# SCH_NFC-Business-Card_2025-04-14.net
KiCad netlist of a schematic drawn in EasyEDA
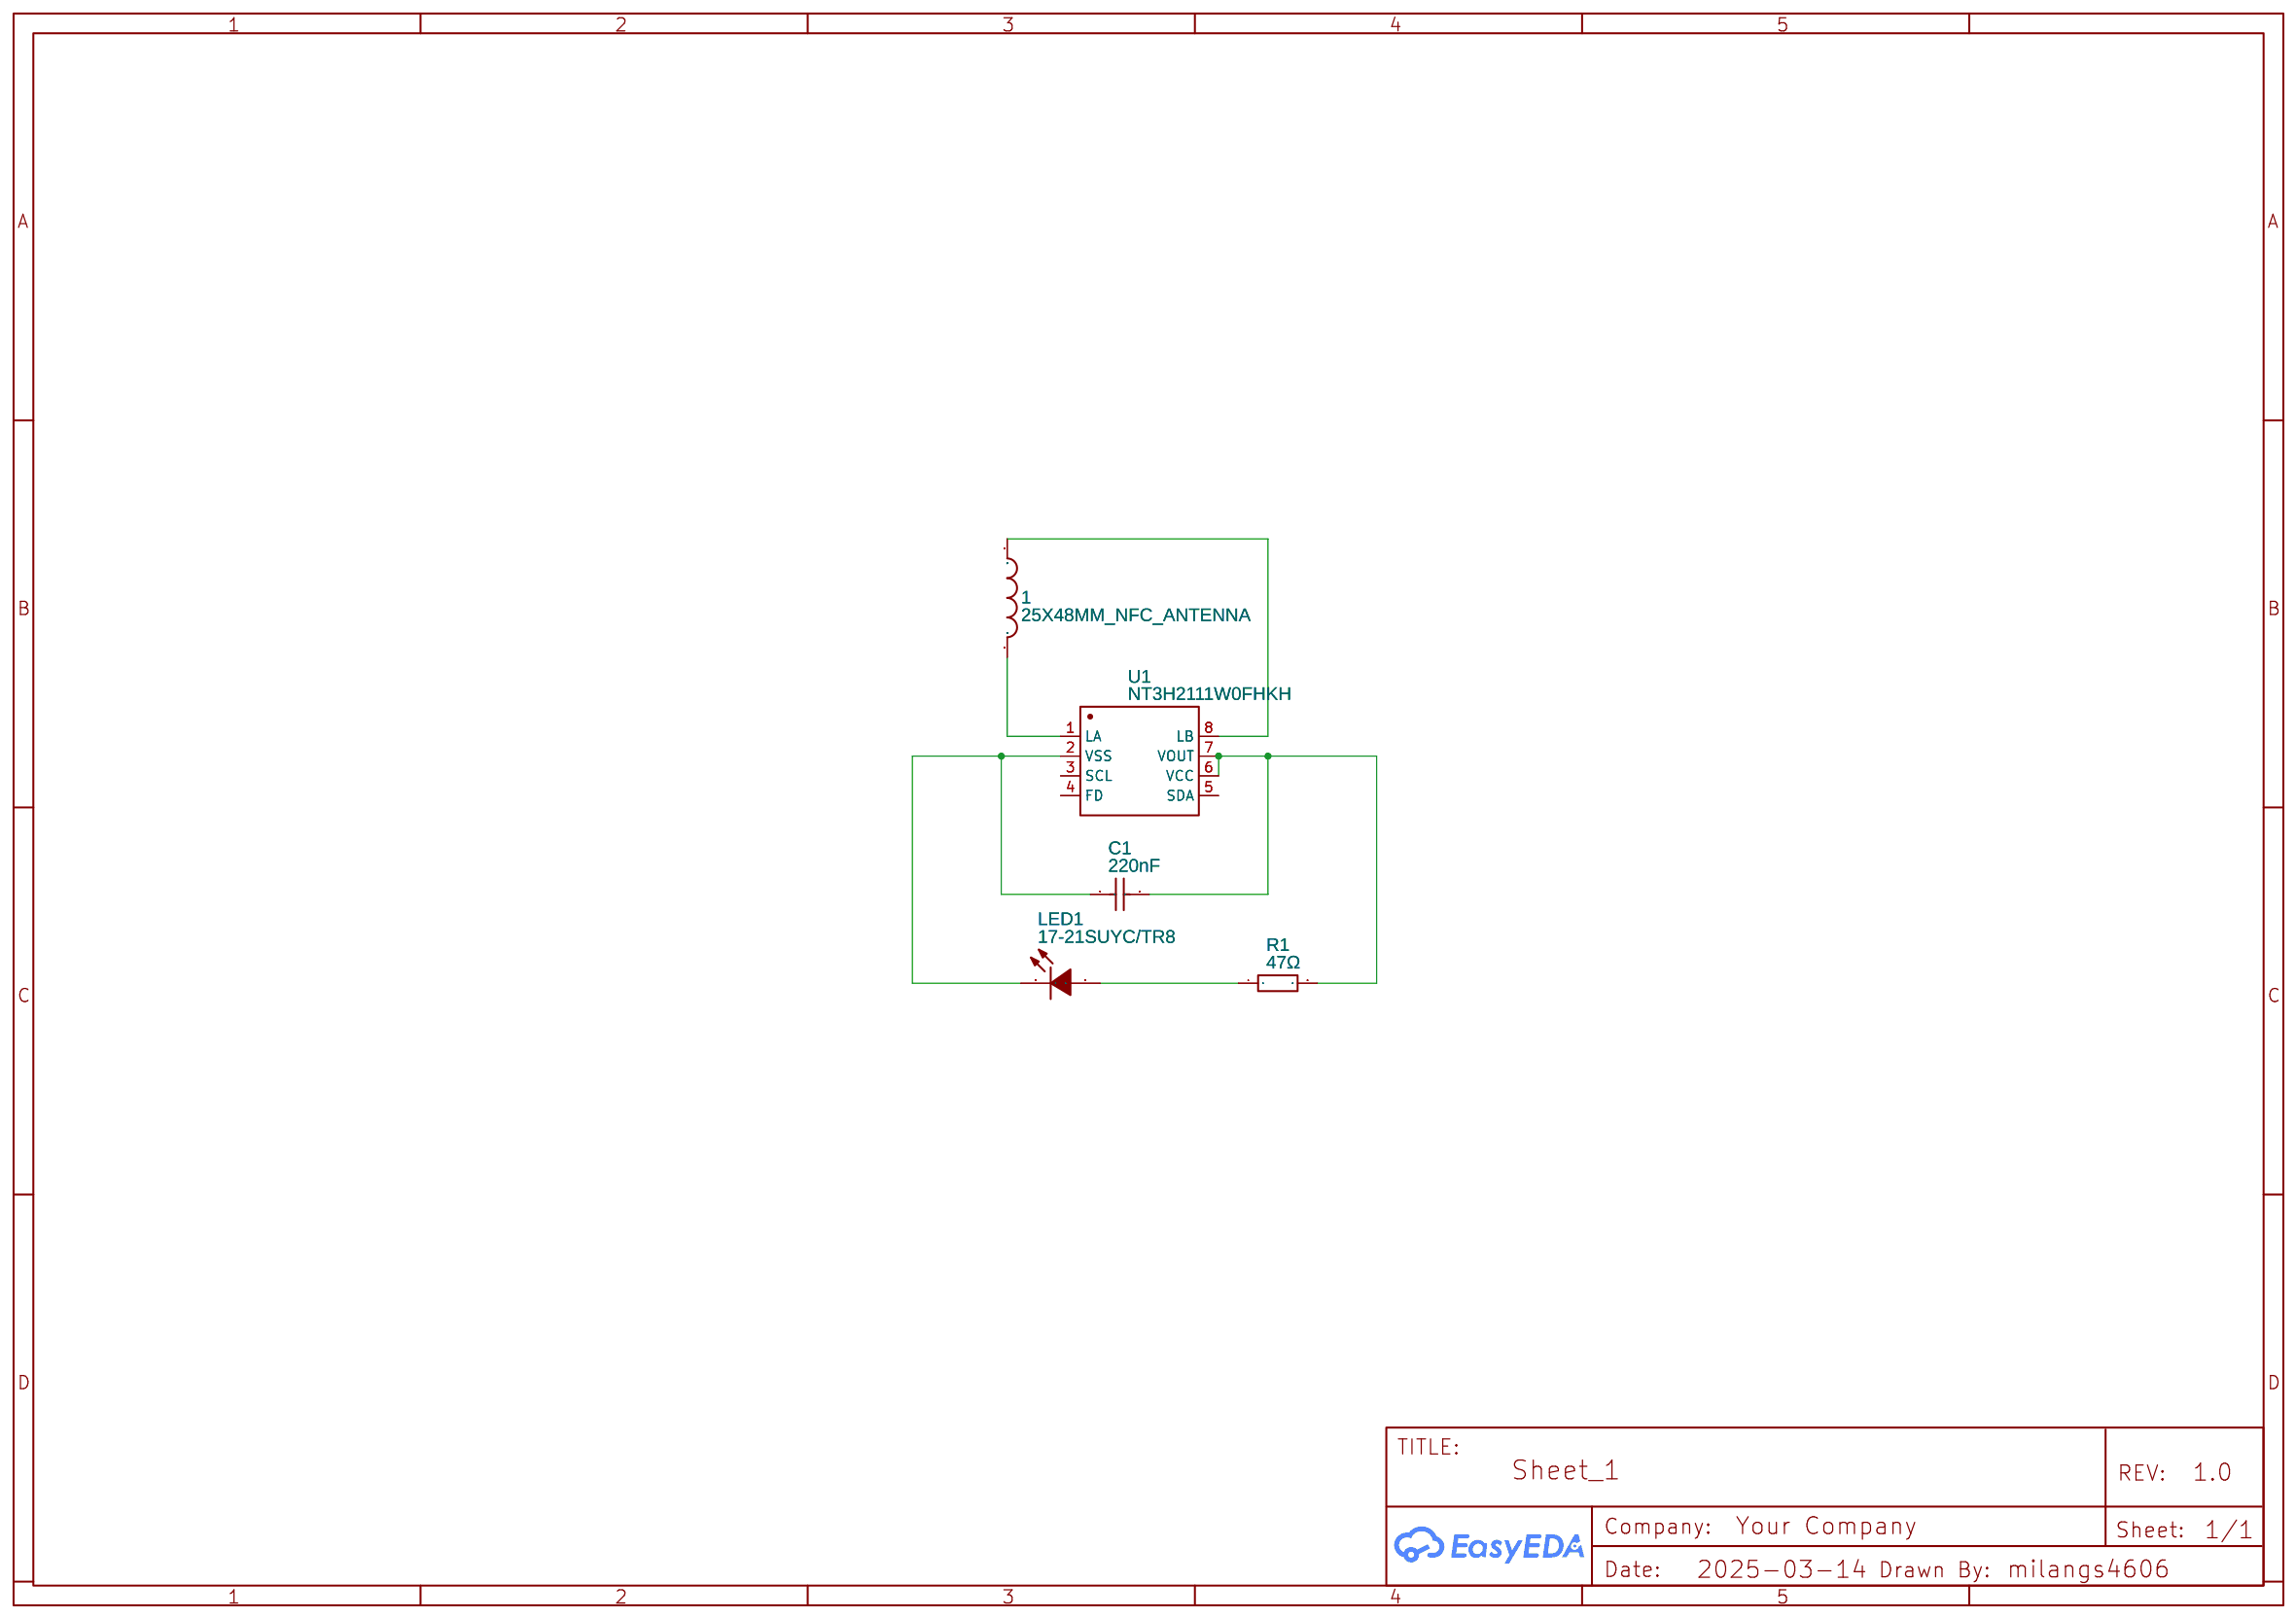
[diagram p0: schematic sheet]

(export (version "E")
  (design (tool "Eeschema 10.0.6"))
  (components
    (comp (ref "1") (value "25X48MM_NFC_ANTENNA") (libsource (lib "") (part "25X48MM_NFC_ANTENNA")))
    (comp (ref "C1")
      (value "220nF")
      (fields
        (field (name "Manufacturer Part") "CL10B224KA8NNNC")
        (field (name "Manufacturer") "SAMSUNG(三星)")
      )
      (libsource (lib "") (part "CL10B224KA8NNNC"))
    )
    (comp (ref "LED1")
      (value "17-21SUYC/TR8")
      (fields (field (name "Manufacturer Part") "KT-0805黄灯") (field (name "Manufacturer") "KENTO"))
      (libsource (lib "") (part "17-21SUYC/TR8"))
    )
    (comp (ref "R1")
      (value "47Ω")
      (fields
        (field (name "Manufacturer Part") "0603WAF470JT5E")
        (field (name "Manufacturer") "UNI-ROYAL(厚声)")
      )
      (libsource (lib "") (part "0603WAF470JT5E"))
    )
    (comp (ref "U1")
      (value "NT3H2111W0FHKH")
      (fields (field (name "Manufacturer") "NXP(恩智浦)"))
      (libsource (lib "") (part "NT3H2111W0FHKH"))
    )
  )
  (nets
    (net (code "1") (name "Net-(LED1-+)") (class "Default")
      (node (ref "LED1") (pin "1") (pinfunction "+_1") (pintype "unspecified"))
      (node (ref "R1") (pin "1") (pinfunction "1_1") (pintype "input"))
    )
    (net (code "2") (name "Net-(LED1--)") (class "Default")
      (node (ref "C1") (pin "1") (pinfunction "1_1") (pintype "input"))
      (node (ref "LED1") (pin "2") (pinfunction "-_2") (pintype "unspecified"))
      (node (ref "U1") (pin "2") (pinfunction "VSS_2") (pintype "unspecified"))
    )
    (net (code "3") (name "Net-(U1-LA)") (class "Default")
      (node (ref "1") (pin "P$2") (pinfunction "P$2_P$2") (pintype "bidirectional"))
      (node (ref "U1") (pin "1") (pinfunction "LA_1") (pintype "unspecified"))
    )
    (net (code "4") (name "Net-(U1-LB)") (class "Default")
      (node (ref "1") (pin "P$1") (pinfunction "P$1_P$1") (pintype "bidirectional"))
      (node (ref "U1") (pin "8") (pinfunction "LB_8") (pintype "unspecified"))
    )
    (net (code "5") (name "Net-(U1-VCC)") (class "Default")
      (node (ref "C1") (pin "2") (pinfunction "2_2") (pintype "input"))
      (node (ref "R1") (pin "2") (pinfunction "2_2") (pintype "input"))
      (node (ref "U1") (pin "6") (pinfunction "VCC_6") (pintype "unspecified"))
      (node (ref "U1") (pin "7") (pinfunction "VOUT_7") (pintype "unspecified"))
    )
    (net (code "6") (name "unconnected-(U1-FD-Pad4)") (class "Default")
      (node (ref "U1") (pin "4") (pinfunction "FD_4") (pintype "unspecified"))
    )
    (net (code "7") (name "unconnected-(U1-SCL-Pad3)") (class "Default")
      (node (ref "U1") (pin "3") (pinfunction "SCL_3") (pintype "unspecified"))
    )
    (net (code "8") (name "unconnected-(U1-SDA-Pad5)") (class "Default")
      (node (ref "U1") (pin "5") (pinfunction "SDA_5") (pintype "unspecified"))
    )
  )
)
